# VGA_driver.net
KiCad netlist of a schematic drawn in Altium Designer
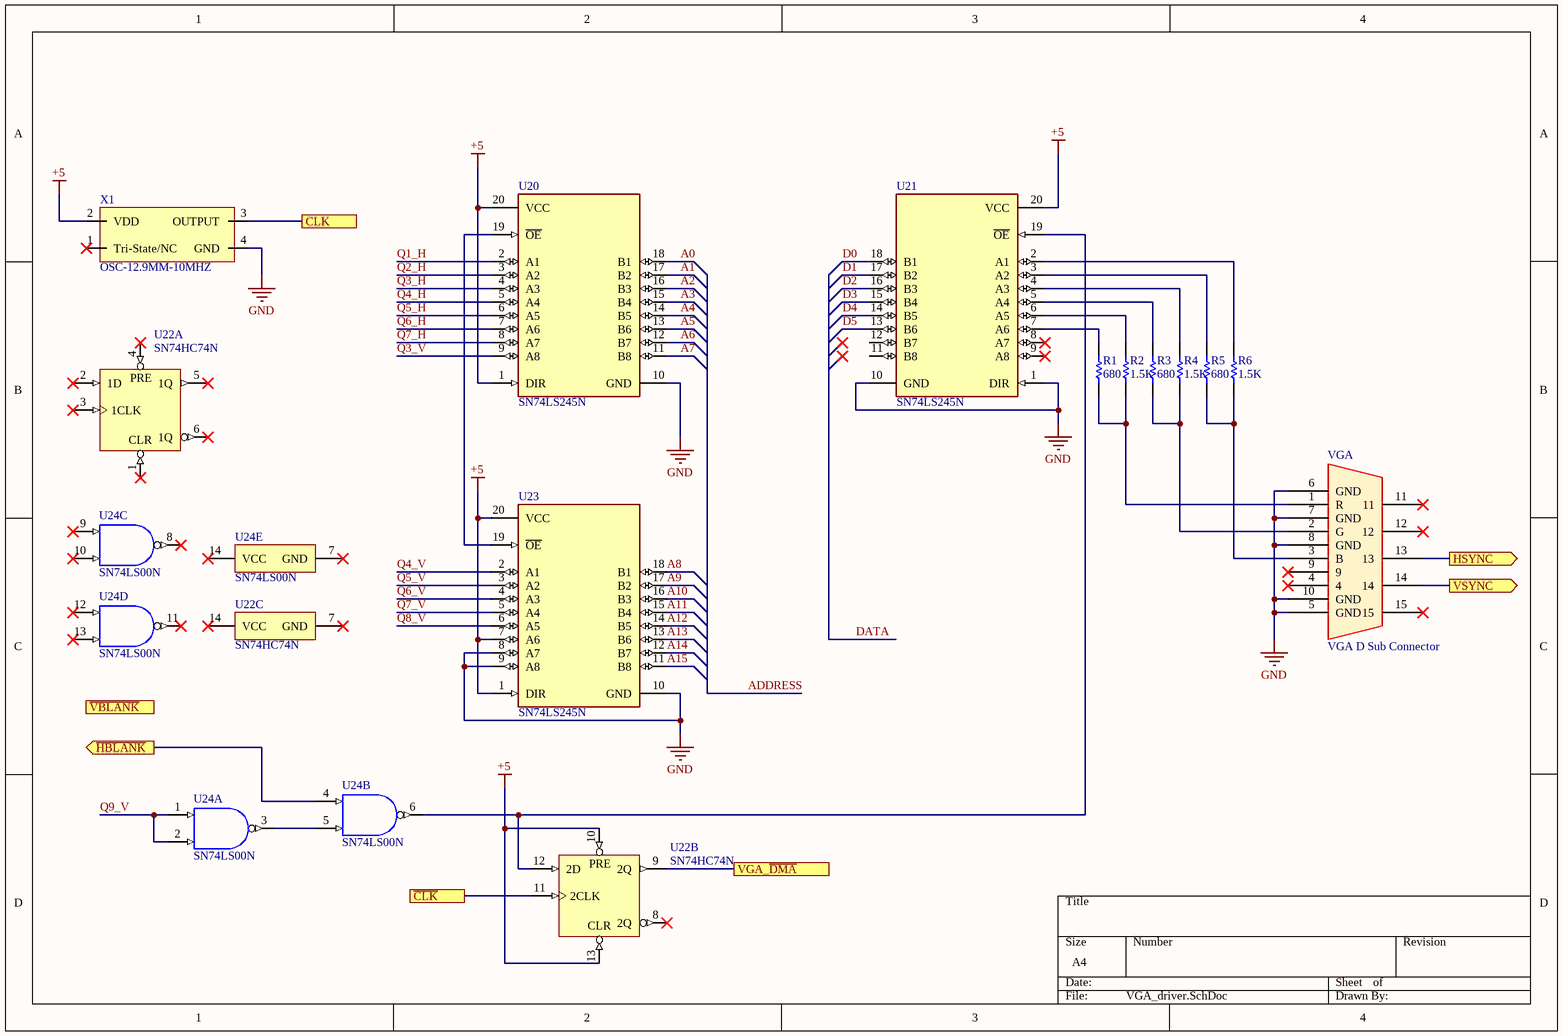
[diagram p0: VGA_driver.SchDoc]

(export (version "E")
  (design (tool "Eeschema 10.0.6"))
  (components
    (comp (ref "R1")
      (value "CRCW0805680RFKEA")
      (footprint "RESC2013X50X30NL20T20")
      (fields (field (name "MANUFACTURER") "Vishay Dale") (field (name "RESISTANCE") "680"))
      (libsource (lib "Altium Content Vault") (part "RES"))
    )
    (comp (ref "R2")
      (value "RC0805FR-071K5L")
      (footprint "RESC2013X60X35LL10T20")
      (description "RES 1.50K OHM 1/8W 1% 0805 SMD")
      (fields (field (name "MANUFACTURER") "Yageo") (field (name "RESISTANCE") "1.5K"))
      (libsource (lib "Altium Content Vault") (part "RES-2"))
    )
    (comp (ref "R3")
      (value "CRCW0805680RFKEA")
      (footprint "RESC2013X50X30NL20T20")
      (fields (field (name "MANUFACTURER") "Vishay Dale") (field (name "RESISTANCE") "680"))
      (libsource (lib "Altium Content Vault") (part "RES"))
    )
    (comp (ref "R4")
      (value "RC0805FR-071K5L")
      (footprint "RESC2013X60X35LL10T20")
      (description "RES 1.50K OHM 1/8W 1% 0805 SMD")
      (fields (field (name "MANUFACTURER") "Yageo") (field (name "RESISTANCE") "1.5K"))
      (libsource (lib "Altium Content Vault") (part "RES-2"))
    )
    (comp (ref "R5")
      (value "CRCW0805680RFKEA")
      (footprint "RESC2013X50X30NL20T20")
      (fields (field (name "MANUFACTURER") "Vishay Dale") (field (name "RESISTANCE") "680"))
      (libsource (lib "Altium Content Vault") (part "RES"))
    )
    (comp (ref "R6")
      (value "RC0805FR-071K5L")
      (footprint "RESC2013X60X35LL10T20")
      (description "RES 1.50K OHM 1/8W 1% 0805 SMD")
      (fields (field (name "MANUFACTURER") "Yageo") (field (name "RESISTANCE") "1.5K"))
      (libsource (lib "Altium Content Vault") (part "RES-2"))
    )
    (comp (ref "U20")
      (value "SN74LS245N")
      (footprint "FP-N0020A-MFG")
      (description "IC TXRX NON-INVERT 5.25V 20DIP")
      (libsource (lib "Altium Content Vault") (part "10c8780e4db4806136f4ae6e668cc9c"))
    )
    (comp (ref "U21")
      (value "SN74LS245N")
      (footprint "FP-N0020A-MFG")
      (description "IC TXRX NON-INVERT 5.25V 20DIP")
      (libsource (lib "") (part "10c8780e4db4806136f4ae6e668cc9c_1"))
    )
    (comp (ref "U22")
      (value "SN74HC74N")
      (footprint "N0014A")
      (description "Dual D-Type Positive-Edge-Triggered Flip-Flops With Clear and Preset, N0014A, TUBE")
      (fields
        (field (name "MANUFACTURER") "Texas Instruments")
        (field (name "GENERIC PART NUMBER") "SN74HC74")
      )
      (libsource (lib "Altium Content Vault") (part "TI-CD_SNX4XXXX74X-14"))
    )
    (comp (ref "U23")
      (value "SN74LS245N")
      (footprint "FP-N0020A-MFG")
      (description "IC TXRX NON-INVERT 5.25V 20DIP")
      (libsource (lib "Altium Content Vault") (part "10c8780e4db4806136f4ae6e668cc9c"))
    )
    (comp (ref "U24")
      (value "SN74LS00N")
      (footprint "N0014A")
      (description "Quad 2-input positive-NAND gates, N0014A, TUBE")
      (fields
        (field (name "MANUFACTURER") "Texas Instruments")
        (field (name "GENERIC PART NUMBER") "SN74LS00")
      )
      (libsource (lib "Altium Content Vault") (part "TI-NAND-4-2IN-14_G"))
    )
    (comp (ref "VGA")
      (value "VGA D Sub Connector")
      (footprint "VGA")
      (libsource (lib "6502_lib") (part "VGA-002"))
    )
    (comp (ref "X1")
      (value "OSC-12.9MM-10MHZ")
      (footprint "OSC_THT_12-9MM")
      (description "12.9MM x 12.9MM, 1MHz Can Oscillator")
      (libsource (lib "6502_lib") (part "OSC-12.9MM-1MHZ"))
    )
  )
  (nets
    (net (code "3") (name "+5") (class "Default")
      (node (ref "U20") (pin "1") (pinfunction "DIR_1") (pintype "input"))
      (node (ref "U20") (pin "20") (pinfunction "VCC_20") (pintype "power_in"))
      (node (ref "U21") (pin "20") (pinfunction "VCC_20") (pintype "power_in"))
      (node (ref "U22") (pin "10") (pinfunction "2~{PRE}_10") (pintype "input"))
      (node (ref "U22") (pin "13") (pinfunction "2~{CLR}_13") (pintype "input"))
      (node (ref "U23") (pin "1") (pinfunction "DIR_1") (pintype "input"))
      (node (ref "U23") (pin "20") (pinfunction "VCC_20") (pintype "power_in"))
      (node (ref "U23") (pin "7") (pinfunction "A6_7") (pintype "bidirectional"))
      (node (ref "X1") (pin "2") (pinfunction "VDD_2") (pintype "passive"))
    )
    (net (code "4") (name "/A0") (class "Default")
      (node (ref "U20") (pin "18") (pinfunction "B1_18") (pintype "bidirectional"))
    )
    (net (code "5") (name "/A1") (class "Default")
      (node (ref "U20") (pin "17") (pinfunction "B2_17") (pintype "bidirectional"))
    )
    (net (code "6") (name "/A2") (class "Default")
      (node (ref "U20") (pin "16") (pinfunction "B3_16") (pintype "bidirectional"))
    )
    (net (code "7") (name "/A3") (class "Default")
      (node (ref "U20") (pin "15") (pinfunction "B4_15") (pintype "bidirectional"))
    )
    (net (code "8") (name "/A4") (class "Default")
      (node (ref "U20") (pin "14") (pinfunction "B5_14") (pintype "bidirectional"))
    )
    (net (code "9") (name "/A5") (class "Default")
      (node (ref "U20") (pin "13") (pinfunction "B6_13") (pintype "bidirectional"))
    )
    (net (code "10") (name "/A6") (class "Default")
      (node (ref "U20") (pin "12") (pinfunction "B7_12") (pintype "bidirectional"))
    )
    (net (code "11") (name "/A7") (class "Default")
      (node (ref "U20") (pin "11") (pinfunction "B8_11") (pintype "bidirectional"))
    )
    (net (code "12") (name "/A8") (class "Default")
      (node (ref "U23") (pin "18") (pinfunction "B1_18") (pintype "bidirectional"))
    )
    (net (code "13") (name "/A9") (class "Default")
      (node (ref "U23") (pin "17") (pinfunction "B2_17") (pintype "bidirectional"))
    )
    (net (code "14") (name "/A10") (class "Default")
      (node (ref "U23") (pin "16") (pinfunction "B3_16") (pintype "bidirectional"))
    )
    (net (code "15") (name "/A11") (class "Default")
      (node (ref "U23") (pin "15") (pinfunction "B4_15") (pintype "bidirectional"))
    )
    (net (code "16") (name "/A12") (class "Default")
      (node (ref "U23") (pin "14") (pinfunction "B5_14") (pintype "bidirectional"))
    )
    (net (code "17") (name "/A13") (class "Default")
      (node (ref "U23") (pin "13") (pinfunction "B6_13") (pintype "bidirectional"))
    )
    (net (code "18") (name "/A14") (class "Default")
      (node (ref "U23") (pin "12") (pinfunction "B7_12") (pintype "bidirectional"))
    )
    (net (code "19") (name "/A15") (class "Default")
      (node (ref "U23") (pin "11") (pinfunction "B8_11") (pintype "bidirectional"))
    )
    (net (code "20") (name "/CLK") (class "Default")
      (node (ref "X1") (pin "3") (pinfunction "OUTPUT_3") (pintype "passive"))
    )
    (net (code "21") (name "/D0") (class "Default")
      (node (ref "U21") (pin "18") (pinfunction "B1_18") (pintype "bidirectional"))
    )
    (net (code "22") (name "/D1") (class "Default")
      (node (ref "U21") (pin "17") (pinfunction "B2_17") (pintype "bidirectional"))
    )
    (net (code "23") (name "/D2") (class "Default")
      (node (ref "U21") (pin "16") (pinfunction "B3_16") (pintype "bidirectional"))
    )
    (net (code "24") (name "/D3") (class "Default")
      (node (ref "U21") (pin "15") (pinfunction "B4_15") (pintype "bidirectional"))
    )
    (net (code "25") (name "/D4") (class "Default")
      (node (ref "U21") (pin "14") (pinfunction "B5_14") (pintype "bidirectional"))
    )
    (net (code "26") (name "/D5") (class "Default")
      (node (ref "U21") (pin "13") (pinfunction "B6_13") (pintype "bidirectional"))
    )
    (net (code "27") (name "/HSYNC") (class "Default")
      (node (ref "VGA") (pin "13") (pinfunction "13_13") (pintype "passive"))
    )
    (net (code "28") (name "/Q1_H") (class "Default")
      (node (ref "U20") (pin "2") (pinfunction "A1_2") (pintype "bidirectional"))
    )
    (net (code "29") (name "/Q2_H") (class "Default")
      (node (ref "U20") (pin "3") (pinfunction "A2_3") (pintype "bidirectional"))
    )
    (net (code "30") (name "/Q3_H") (class "Default")
      (node (ref "U20") (pin "4") (pinfunction "A3_4") (pintype "bidirectional"))
    )
    (net (code "31") (name "/Q3_V") (class "Default")
      (node (ref "U20") (pin "9") (pinfunction "A8_9") (pintype "bidirectional"))
    )
    (net (code "32") (name "/Q4_H") (class "Default")
      (node (ref "U20") (pin "5") (pinfunction "A4_5") (pintype "bidirectional"))
    )
    (net (code "33") (name "/Q4_V") (class "Default")
      (node (ref "U23") (pin "2") (pinfunction "A1_2") (pintype "bidirectional"))
    )
    (net (code "34") (name "/Q5_H") (class "Default")
      (node (ref "U20") (pin "6") (pinfunction "A5_6") (pintype "bidirectional"))
    )
    (net (code "35") (name "/Q5_V") (class "Default")
      (node (ref "U23") (pin "3") (pinfunction "A2_3") (pintype "bidirectional"))
    )
    (net (code "36") (name "/Q6_H") (class "Default")
      (node (ref "U20") (pin "7") (pinfunction "A6_7") (pintype "bidirectional"))
    )
    (net (code "37") (name "/Q6_V") (class "Default")
      (node (ref "U23") (pin "4") (pinfunction "A3_4") (pintype "bidirectional"))
    )
    (net (code "38") (name "/Q7_H") (class "Default")
      (node (ref "U20") (pin "8") (pinfunction "A7_8") (pintype "bidirectional"))
    )
    (net (code "39") (name "/Q7_V") (class "Default")
      (node (ref "U23") (pin "5") (pinfunction "A4_5") (pintype "bidirectional"))
    )
    (net (code "40") (name "/Q8_V") (class "Default")
      (node (ref "U23") (pin "6") (pinfunction "A5_6") (pintype "bidirectional"))
    )
    (net (code "41") (name "/Q9_V") (class "Default")
      (node (ref "U24") (pin "1") (pinfunction "1A_1") (pintype "input"))
      (node (ref "U24") (pin "2") (pinfunction "1B_2") (pintype "input"))
    )
    (net (code "42") (name "/VGA_~{DMA}") (class "Default")
      (node (ref "U22") (pin "9") (pinfunction "2Q_9") (pintype "output"))
    )
    (net (code "43") (name "/VSYNC") (class "Default")
      (node (ref "VGA") (pin "14") (pinfunction "14_14") (pintype "passive"))
    )
    (net (code "46") (name "/~{CLK}") (class "Default")
      (node (ref "U22") (pin "11") (pinfunction "2CLK_11") (pintype "input"))
    )
    (net (code "47") (name "/~{HBLANK}") (class "Default")
      (node (ref "U24") (pin "4") (pinfunction "2A_4") (pintype "input"))
    )
    (net (code "49") (name "GND") (class "Default")
      (node (ref "U20") (pin "10") (pinfunction "GND_10") (pintype "power_in"))
      (node (ref "U21") (pin "1") (pinfunction "DIR_1") (pintype "input"))
      (node (ref "U21") (pin "10") (pinfunction "GND_10") (pintype "power_in"))
      (node (ref "U23") (pin "10") (pinfunction "GND_10") (pintype "power_in"))
      (node (ref "U23") (pin "8") (pinfunction "A7_8") (pintype "bidirectional"))
      (node (ref "U23") (pin "9") (pinfunction "A8_9") (pintype "bidirectional"))
      (node (ref "VGA") (pin "10") (pinfunction "GND_10") (pintype "passive"))
      (node (ref "VGA") (pin "5") (pinfunction "GND_5") (pintype "passive"))
      (node (ref "VGA") (pin "6") (pinfunction "GND_6") (pintype "passive"))
      (node (ref "VGA") (pin "7") (pinfunction "GND_7") (pintype "passive"))
      (node (ref "VGA") (pin "8") (pinfunction "GND_8") (pintype "passive"))
      (node (ref "X1") (pin "4") (pinfunction "GND_4") (pintype "passive"))
    )
    (net (code "50") (name "Net-(U20-~{OE})") (class "Default")
      (node (ref "U20") (pin "19") (pinfunction "~{OE}_19") (pintype "input"))
      (node (ref "U23") (pin "19") (pinfunction "~{OE}_19") (pintype "input"))
    )
    (net (code "51") (name "Net-(U21-A1)") (class "Default")
      (node (ref "R6") (pin "2") (pinfunction "2_2") (pintype "passive"))
      (node (ref "U21") (pin "2") (pinfunction "A1_2") (pintype "bidirectional"))
    )
    (net (code "52") (name "Net-(U21-A2)") (class "Default")
      (node (ref "R5") (pin "2") (pinfunction "2_2") (pintype "passive"))
      (node (ref "U21") (pin "3") (pinfunction "A2_3") (pintype "bidirectional"))
    )
    (net (code "53") (name "Net-(U21-A3)") (class "Default")
      (node (ref "R4") (pin "2") (pinfunction "2_2") (pintype "passive"))
      (node (ref "U21") (pin "4") (pinfunction "A3_4") (pintype "bidirectional"))
    )
    (net (code "54") (name "Net-(U21-A4)") (class "Default")
      (node (ref "R3") (pin "2") (pinfunction "2_2") (pintype "passive"))
      (node (ref "U21") (pin "5") (pinfunction "A4_5") (pintype "bidirectional"))
    )
    (net (code "55") (name "Net-(U21-A5)") (class "Default")
      (node (ref "R2") (pin "2") (pinfunction "2_2") (pintype "passive"))
      (node (ref "U21") (pin "6") (pinfunction "A5_6") (pintype "bidirectional"))
    )
    (net (code "56") (name "Net-(U21-A6)") (class "Default")
      (node (ref "R1") (pin "2") (pinfunction "2_2") (pintype "passive"))
      (node (ref "U21") (pin "7") (pinfunction "A6_7") (pintype "bidirectional"))
    )
    (net (code "57") (name "Net-(U21-~{OE})") (class "Default")
      (node (ref "U21") (pin "19") (pinfunction "~{OE}_19") (pintype "input"))
      (node (ref "U22") (pin "12") (pinfunction "2D_12") (pintype "input"))
      (node (ref "U24") (pin "6") (pinfunction "2Y_6") (pintype "output"))
    )
    (net (code "58") (name "Net-(U24A-1Y)") (class "Default")
      (node (ref "U24") (pin "3") (pinfunction "1Y_3") (pintype "output"))
      (node (ref "U24") (pin "5") (pinfunction "2B_5") (pintype "input"))
    )
    (net (code "59") (name "Net-(VGA-B)") (class "Default")
      (node (ref "R5") (pin "1") (pinfunction "1_1") (pintype "passive"))
      (node (ref "R6") (pin "1") (pinfunction "1_1") (pintype "passive"))
      (node (ref "VGA") (pin "3") (pinfunction "B_3") (pintype "passive"))
    )
    (net (code "60") (name "Net-(VGA-G)") (class "Default")
      (node (ref "R3") (pin "1") (pinfunction "1_1") (pintype "passive"))
      (node (ref "R4") (pin "1") (pinfunction "1_1") (pintype "passive"))
      (node (ref "VGA") (pin "2") (pinfunction "G_2") (pintype "passive"))
    )
    (net (code "61") (name "Net-(VGA-R)") (class "Default")
      (node (ref "R1") (pin "1") (pinfunction "1_1") (pintype "passive"))
      (node (ref "R2") (pin "1") (pinfunction "1_1") (pintype "passive"))
      (node (ref "VGA") (pin "1") (pinfunction "R_1") (pintype "passive"))
    )
    (net (code "62") (name "unconnected-(U21-A7-Pad8)") (class "Default")
      (node (ref "U21") (pin "8") (pinfunction "A7_8") (pintype "bidirectional+no_connect"))
    )
    (net (code "63") (name "unconnected-(U21-A8-Pad9)") (class "Default")
      (node (ref "U21") (pin "9") (pinfunction "A8_9") (pintype "bidirectional+no_connect"))
    )
    (net (code "64") (name "unconnected-(U21-B7-Pad12)") (class "Default")
      (node (ref "U21") (pin "12") (pinfunction "B7_12") (pintype "bidirectional"))
    )
    (net (code "65") (name "unconnected-(U21-B8-Pad11)") (class "Default")
      (node (ref "U21") (pin "11") (pinfunction "B8_11") (pintype "bidirectional"))
    )
    (net (code "66") (name "unconnected-(U22A-1CLK-Pad3)") (class "Default")
      (node (ref "U22") (pin "3") (pinfunction "1CLK_3") (pintype "input+no_connect"))
    )
    (net (code "67") (name "unconnected-(U22A-1D-Pad2)") (class "Default")
      (node (ref "U22") (pin "2") (pinfunction "1D_2") (pintype "input+no_connect"))
    )
    (net (code "68") (name "unconnected-(U22A-1Q-Pad5)") (class "Default")
      (node (ref "U22") (pin "5") (pinfunction "1Q_5") (pintype "output+no_connect"))
    )
    (net (code "69") (name "unconnected-(U22A-1Q-Pad6)") (class "Default")
      (node (ref "U22") (pin "6") (pinfunction "1Q_6") (pintype "output+no_connect"))
    )
    (net (code "70") (name "unconnected-(U22A-1~{CLR}-Pad1)") (class "Default")
      (node (ref "U22") (pin "1") (pinfunction "1~{CLR}_1") (pintype "input+no_connect"))
    )
    (net (code "71") (name "unconnected-(U22A-1~{PRE}-Pad4)") (class "Default")
      (node (ref "U22") (pin "4") (pinfunction "1~{PRE}_4") (pintype "input+no_connect"))
    )
    (net (code "72") (name "unconnected-(U22B-2Q-Pad8)") (class "Default")
      (node (ref "U22") (pin "8") (pinfunction "2Q_8") (pintype "output+no_connect"))
    )
    (net (code "73") (name "unconnected-(U22C-GND-Pad7)") (class "Default")
      (node (ref "U22") (pin "7") (pinfunction "GND_7") (pintype "power_in+no_connect"))
    )
    (net (code "74") (name "unconnected-(U22C-VCC-Pad14)") (class "Default")
      (node (ref "U22") (pin "14") (pinfunction "VCC_14") (pintype "power_in+no_connect"))
    )
    (net (code "75") (name "unconnected-(U24C-3A-Pad9)") (class "Default")
      (node (ref "U24") (pin "9") (pinfunction "3A_9") (pintype "input+no_connect"))
    )
    (net (code "76") (name "unconnected-(U24C-3B-Pad10)") (class "Default")
      (node (ref "U24") (pin "10") (pinfunction "3B_10") (pintype "input+no_connect"))
    )
    (net (code "77") (name "unconnected-(U24C-3Y-Pad8)") (class "Default")
      (node (ref "U24") (pin "8") (pinfunction "3Y_8") (pintype "output+no_connect"))
    )
    (net (code "78") (name "unconnected-(U24D-4A-Pad12)") (class "Default")
      (node (ref "U24") (pin "12") (pinfunction "4A_12") (pintype "input+no_connect"))
    )
    (net (code "79") (name "unconnected-(U24D-4B-Pad13)") (class "Default")
      (node (ref "U24") (pin "13") (pinfunction "4B_13") (pintype "input+no_connect"))
    )
    (net (code "80") (name "unconnected-(U24D-4Y-Pad11)") (class "Default")
      (node (ref "U24") (pin "11") (pinfunction "4Y_11") (pintype "output+no_connect"))
    )
    (net (code "81") (name "unconnected-(U24E-GND-Pad7)") (class "Default")
      (node (ref "U24") (pin "7") (pinfunction "GND_7") (pintype "power_in+no_connect"))
    )
    (net (code "82") (name "unconnected-(U24E-VCC-Pad14)") (class "Default")
      (node (ref "U24") (pin "14") (pinfunction "VCC_14") (pintype "power_in+no_connect"))
    )
    (net (code "83") (name "unconnected-(VGA-Pad4)") (class "Default")
      (node (ref "VGA") (pin "4") (pinfunction "4_4") (pintype "passive+no_connect"))
    )
    (net (code "84") (name "unconnected-(VGA-Pad9)") (class "Default")
      (node (ref "VGA") (pin "9") (pinfunction "9_9") (pintype "passive+no_connect"))
    )
    (net (code "85") (name "unconnected-(VGA-Pad11)") (class "Default")
      (node (ref "VGA") (pin "11") (pinfunction "11_11") (pintype "passive+no_connect"))
    )
    (net (code "86") (name "unconnected-(VGA-Pad12)") (class "Default")
      (node (ref "VGA") (pin "12") (pinfunction "12_12") (pintype "passive+no_connect"))
    )
    (net (code "87") (name "unconnected-(VGA-Pad15)") (class "Default")
      (node (ref "VGA") (pin "15") (pinfunction "15_15") (pintype "passive+no_connect"))
    )
    (net (code "88") (name "unconnected-(X1-Tri-State{slash}NC-Pad1)") (class "Default")
      (node (ref "X1") (pin "1") (pinfunction "Tri-State/NC_1") (pintype "passive+no_connect"))
    )
  )
)
